# 3v3_VR.net
KiCad netlist of a schematic drawn in EAGLE
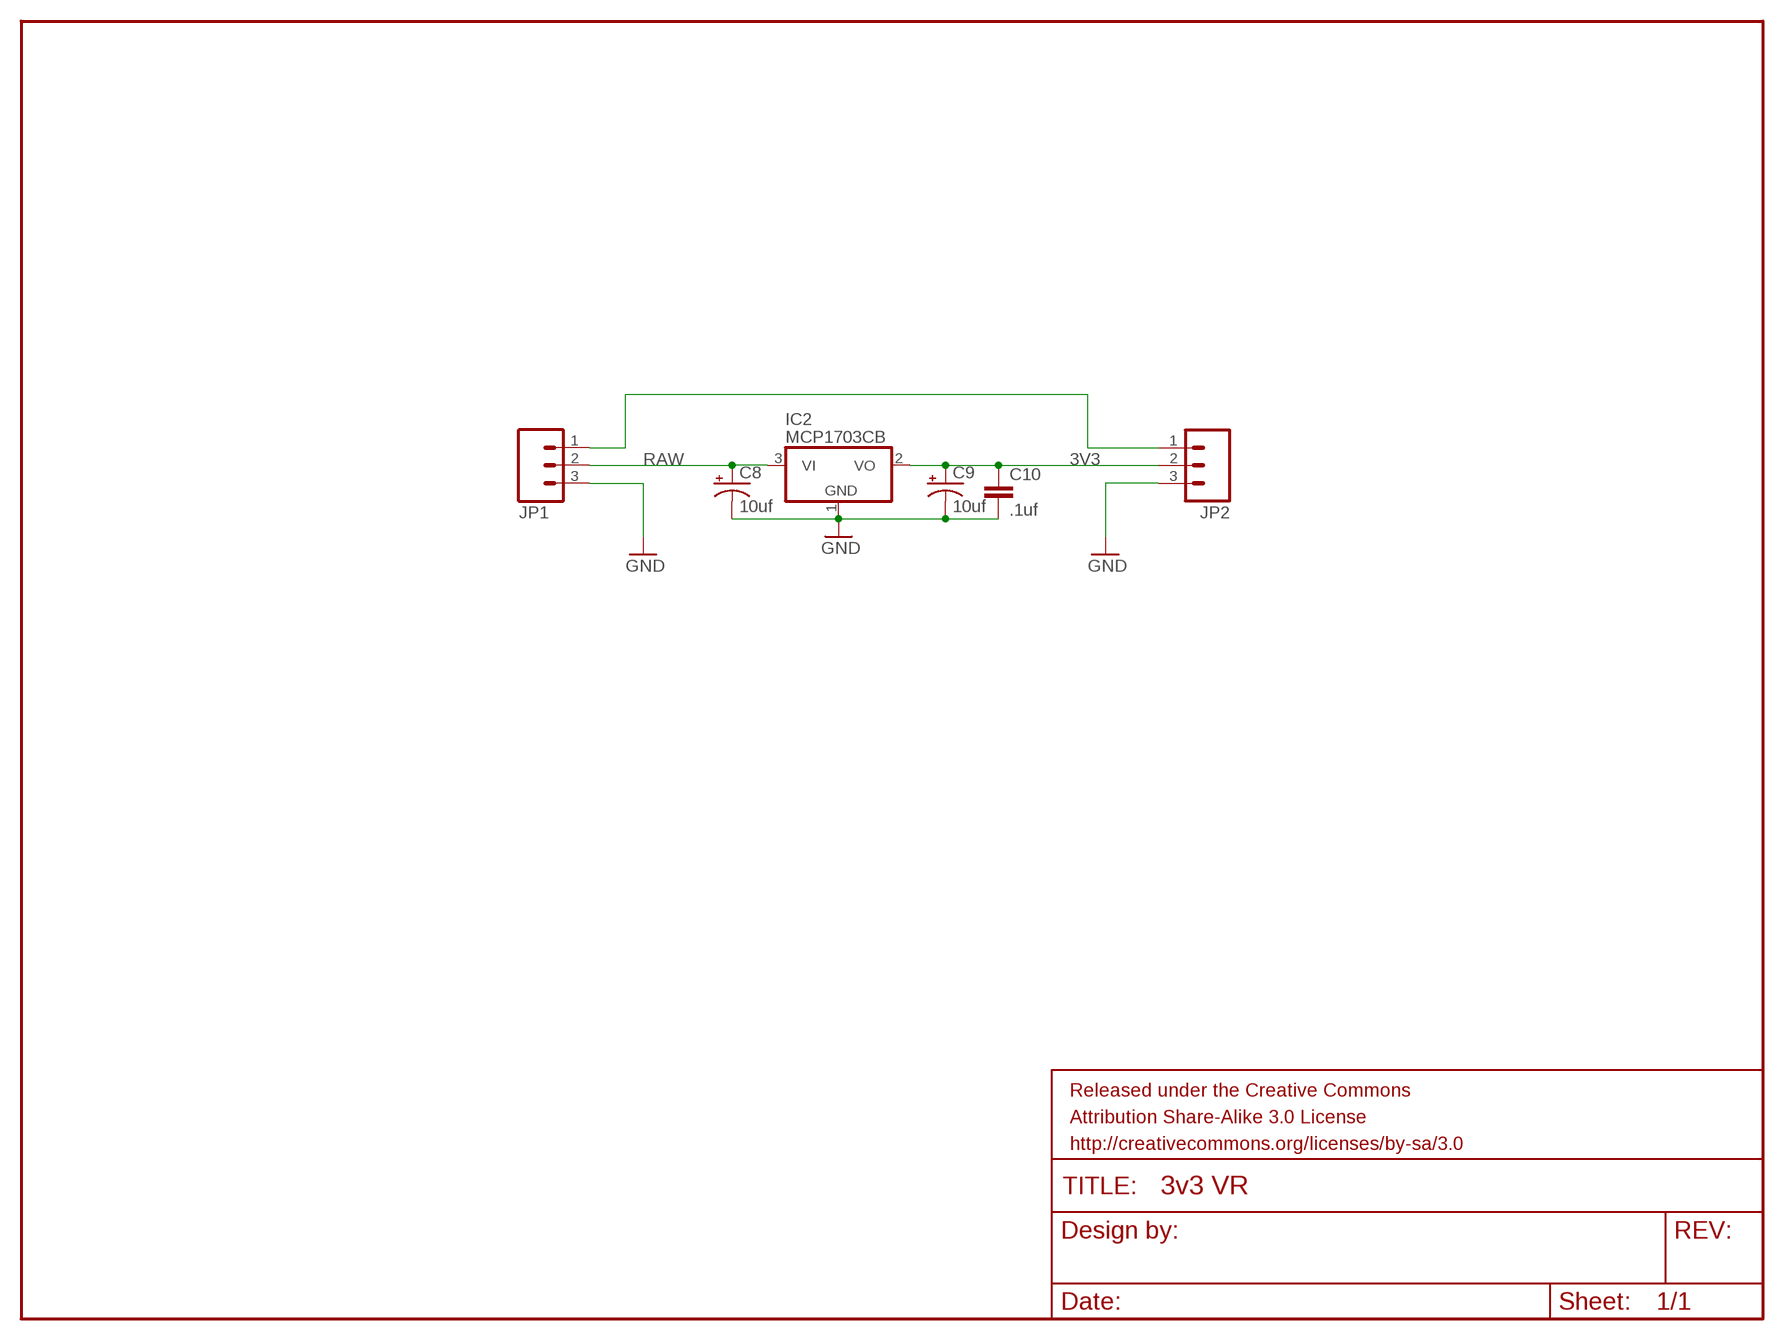
[diagram p0: schematic, sheet 1]

(export (version "E")
  (design (tool "Eeschema 10.0.6"))
  (components
    (comp (ref "C8")
      (value "10uf")
      (footprint "eagle-import:EIA3216")
      (libsource (lib "eagle-import") (part "CAP_POL1206"))
    )
    (comp (ref "C9")
      (value "10uf")
      (footprint "eagle-import:EIA3216")
      (libsource (lib "eagle-import") (part "CAP_POL1206"))
    )
    (comp (ref "C10")
      (value ".1uf")
      (footprint "eagle-import:0402-CAP")
      (libsource (lib "eagle-import") (part "CAP0402-CAP"))
    )
    (comp (ref "FRAME1")
      (value "FRAME-LETTER")
      (footprint "eagle-import:CREATIVE_COMMONS")
      (libsource (lib "eagle-import") (part "FRAME-LETTER"))
    )
    (comp (ref "IC2")
      (value "MCP1703CB")
      (footprint "eagle-import:SOT23")
      (libsource (lib "eagle-import") (part "MCP1703CB"))
    )
    (comp (ref "JP1")
      (value "M031X03_NO_SILK")
      (footprint "eagle-import:1X03_NO_SILK")
      (libsource (lib "eagle-import") (part "M031X03_NO_SILK"))
    )
    (comp (ref "JP2")
      (value "M031X03_NO_SILK")
      (footprint "eagle-import:1X03_NO_SILK")
      (libsource (lib "eagle-import") (part "M031X03_NO_SILK"))
    )
  )
  (nets
    (net (code "1") (name "/3V3") (class "Default")
      (node (ref "C10") (pin "1") (pinfunction "1_1") (pintype "passive"))
      (node (ref "C9") (pin "A") (pinfunction "+_A") (pintype "passive"))
      (node (ref "IC2") (pin "2") (pinfunction "VO_2") (pintype "passive"))
      (node (ref "JP2") (pin "2") (pinfunction "2_2") (pintype "passive"))
    )
    (net (code "2") (name "/RAW") (class "Default")
      (node (ref "C8") (pin "A") (pinfunction "+_A") (pintype "passive"))
      (node (ref "IC2") (pin "3") (pinfunction "VI_3") (pintype "input"))
      (node (ref "JP1") (pin "2") (pinfunction "2_2") (pintype "passive"))
    )
    (net (code "3") (name "GND") (class "Default")
      (node (ref "C10") (pin "2") (pinfunction "2_2") (pintype "passive"))
      (node (ref "C8") (pin "C") (pinfunction "-_C") (pintype "passive"))
      (node (ref "C9") (pin "C") (pinfunction "-_C") (pintype "passive"))
      (node (ref "IC2") (pin "1") (pinfunction "GND_1") (pintype "passive"))
      (node (ref "JP1") (pin "3") (pinfunction "3_3") (pintype "passive"))
      (node (ref "JP2") (pin "3") (pinfunction "3_3") (pintype "passive"))
    )
    (net (code "4") (name "Net-(JP1-Pad1)") (class "Default")
      (node (ref "JP1") (pin "1") (pinfunction "1_1") (pintype "passive"))
      (node (ref "JP2") (pin "1") (pinfunction "1_1") (pintype "passive"))
    )
  )
)
